# SCH_cool-title_2025-03-12.net
KiCad netlist of a schematic drawn in EasyEDA
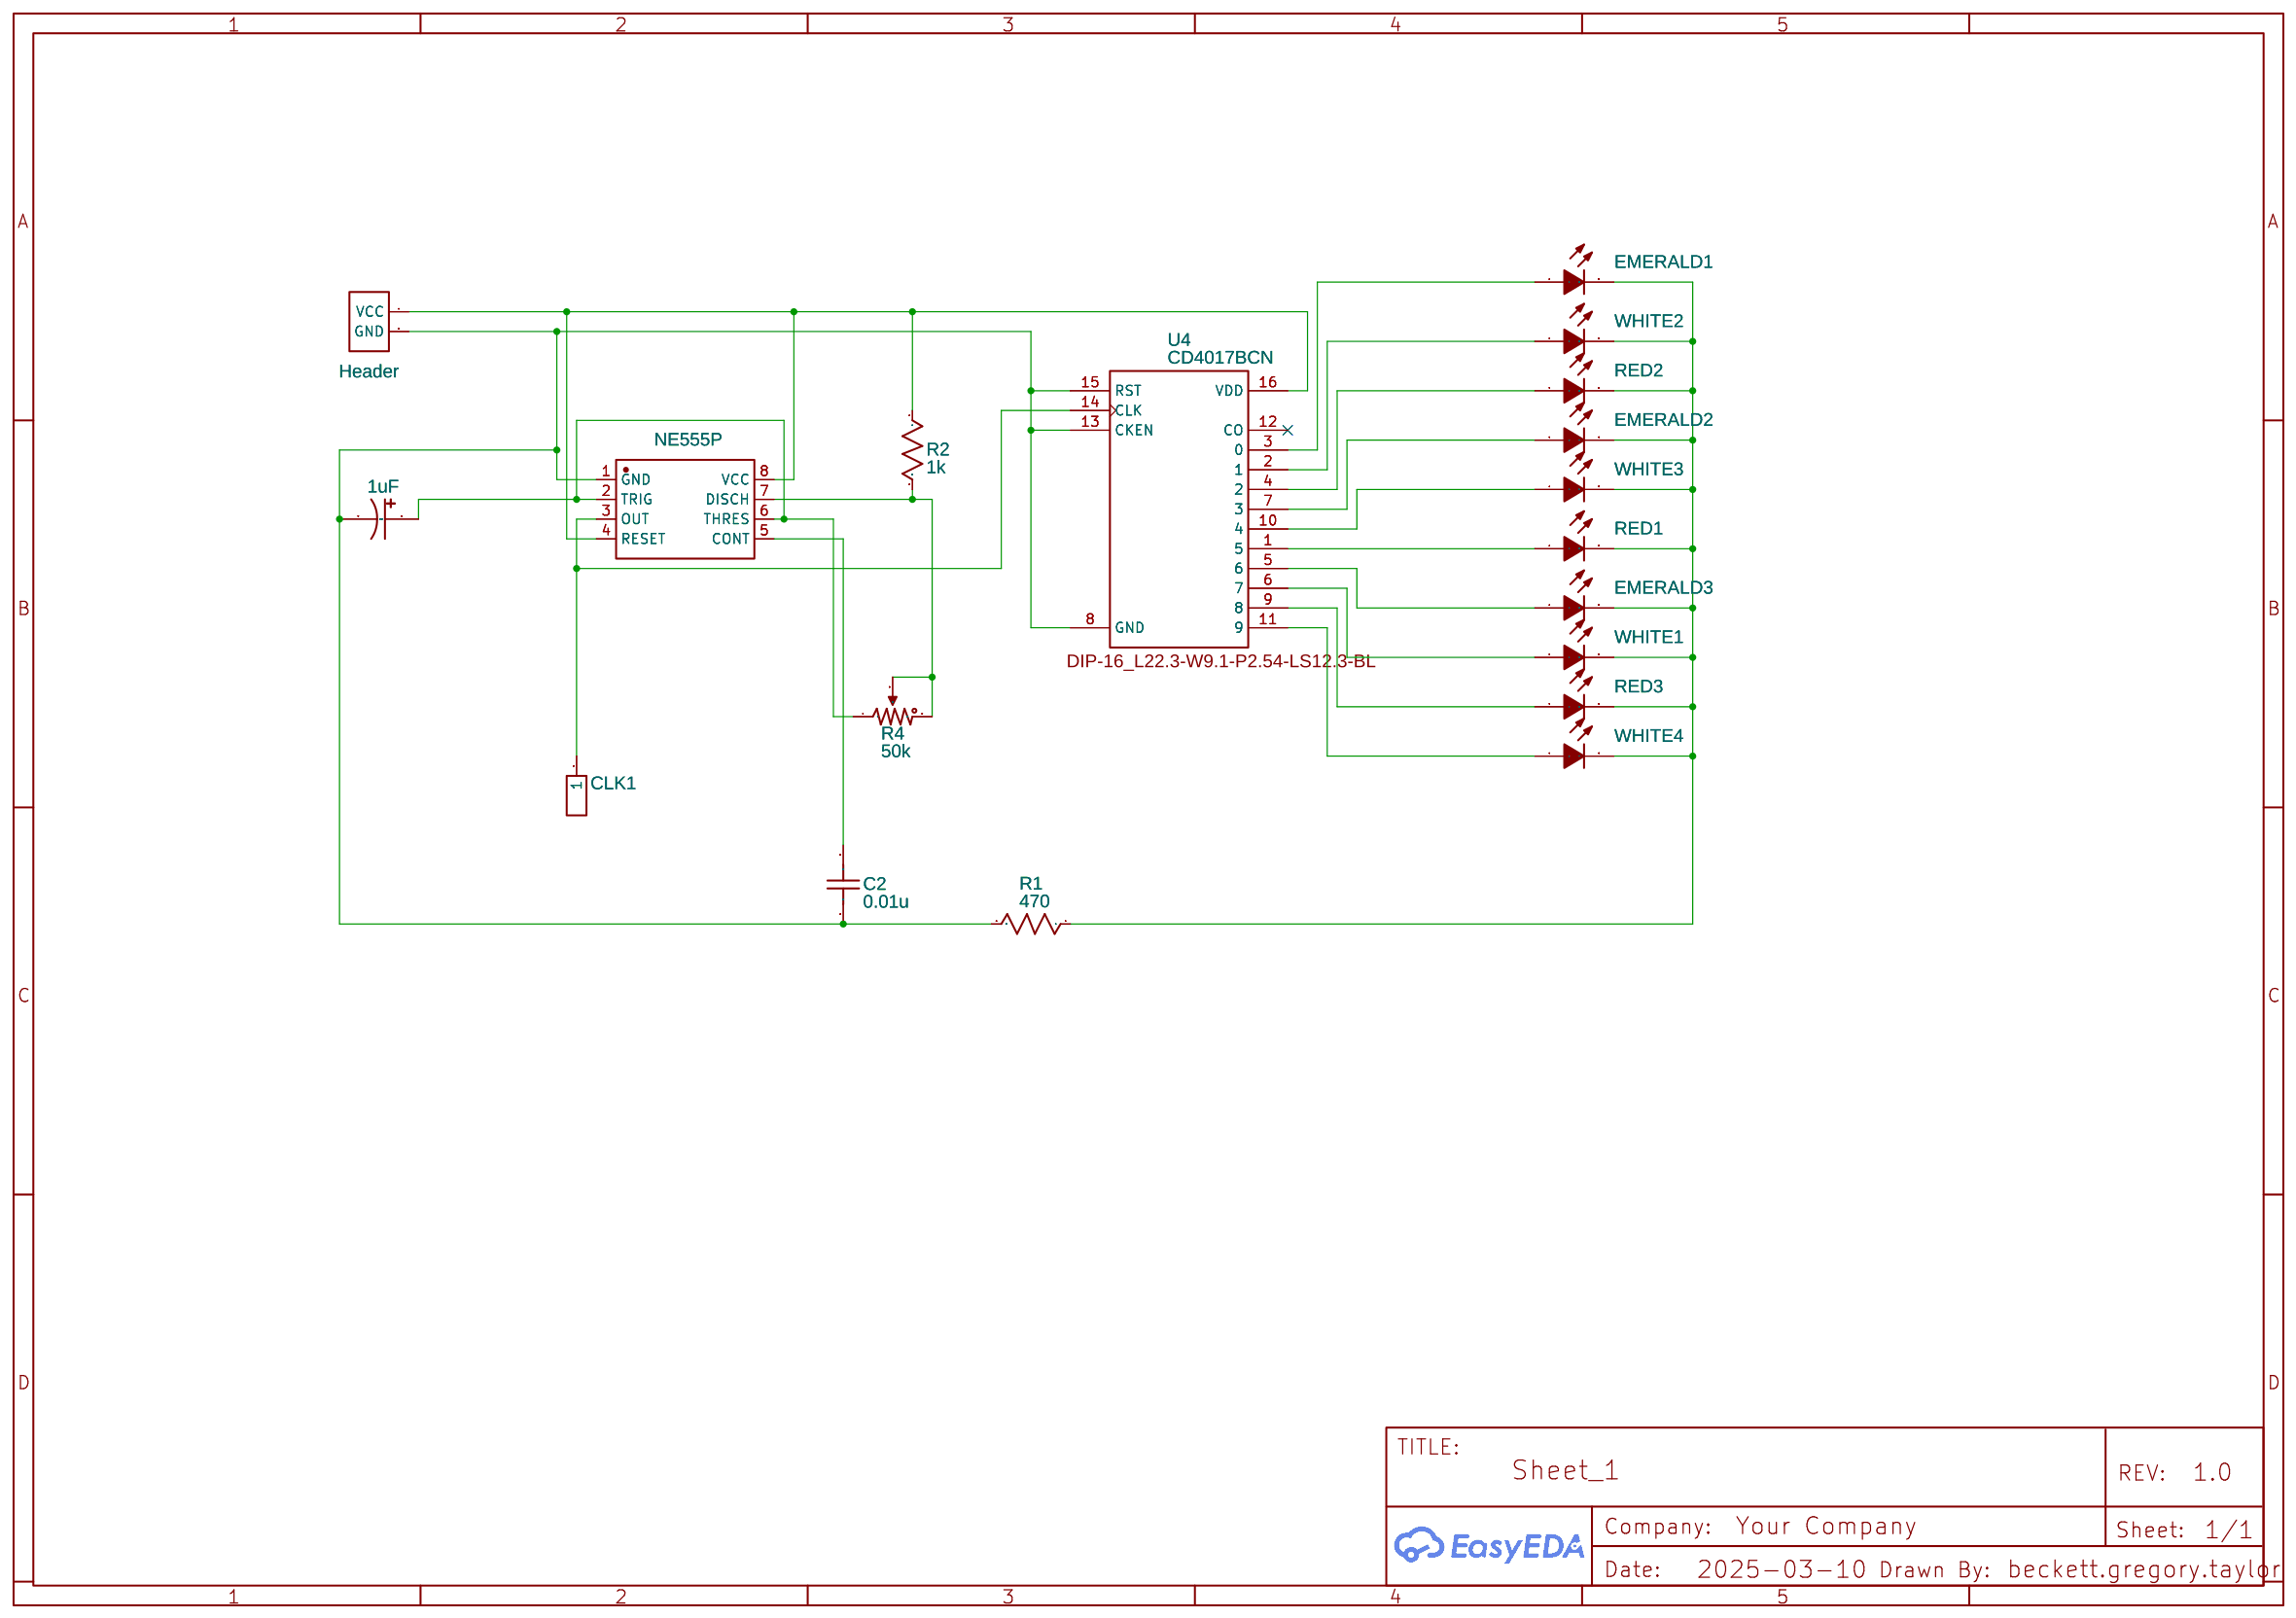
[diagram p0: schematic sheet]

(export (version "E")
  (design (tool "Eeschema 10.0.6"))
  (components
    (comp (ref "C1")
      (value "1uF")
      (fields (field (name "Manufacturer Part") "UVZ1H010MDD") (field (name "Manufacturer") "Nichicon(尼吉康)"))
      (libsource (lib "") (part "UVZ1H010MDD"))
    )
    (comp (ref "C2") (value "0.01u") (libsource (lib "") (part "C_0603_US")))
    (comp (ref "CLK1")
      (value "C81276")
      (fields
        (field (name "Manufacturer Part") "2.54-1*1P针")
        (field (name "Manufacturer") "BOOMELE(Boom Precision Elec)")
      )
      (libsource (lib "") (part "Header-Male-2.54_1x1"))
    )
    (comp (ref "EMERALD1") (value "LED_5MM") (libsource (lib "") (part "LED_5MM_2")))
    (comp (ref "EMERALD2") (value "LED_5MM") (libsource (lib "") (part "LED_5MM_2")))
    (comp (ref "EMERALD3") (value "LED_5MM") (libsource (lib "") (part "LED_5MM_2")))
    (comp (ref "H1") (value "Header") (libsource (lib "") (part "HEADER-FEMALE-2.54_1X2")))
    (comp (ref "R1")
      (value "470")
      (fields (field (name "Manufacturer Part") "?"))
      (libsource (lib "") (part "Resistor"))
    )
    (comp (ref "R2")
      (value "1k")
      (fields (field (name "Manufacturer Part") "?"))
      (libsource (lib "") (part "Resistor_1"))
    )
    (comp (ref "R4")
      (value "50k")
      (fields (field (name "Manufacturer Part") "?"))
      (libsource (lib "") (part "Potentiometer"))
    )
    (comp (ref "RED1") (value "LED_5MM") (libsource (lib "") (part "LED_5MM")))
    (comp (ref "RED2") (value "LED_5MM") (libsource (lib "") (part "LED_5MM")))
    (comp (ref "RED3") (value "LED_5MM") (libsource (lib "") (part "LED_5MM")))
    (comp (ref "U2")
      (value "NE555P")
      (fields (field (name "Manufacturer") "TI(德州仪器)"))
      (libsource (lib "") (part "NE555P"))
    )
    (comp (ref "U4") (value "CD4017BCN") (libsource (lib "") (part "CD4017BCN")))
    (comp (ref "WHITE1") (value "LED_5MM") (libsource (lib "") (part "LED_5MM_1")))
    (comp (ref "WHITE2") (value "LED_5MM") (libsource (lib "") (part "LED_5MM_1")))
    (comp (ref "WHITE3") (value "LED_5MM") (libsource (lib "") (part "LED_5MM_1")))
    (comp (ref "WHITE4") (value "LED_5MM") (libsource (lib "") (part "LED_5MM_1")))
  )
  (nets
    (net (code "1") (name "Net-(EMERALD1-A)") (class "Default")
      (node (ref "EMERALD1") (pin "1") (pinfunction "A_1") (pintype "input"))
      (node (ref "U4") (pin "3") (pinfunction "0_3") (pintype "output"))
    )
    (net (code "2") (name "Net-(EMERALD1-K)") (class "Default")
      (node (ref "EMERALD1") (pin "2") (pinfunction "K_2") (pintype "input"))
      (node (ref "EMERALD2") (pin "2") (pinfunction "K_2") (pintype "input"))
      (node (ref "EMERALD3") (pin "2") (pinfunction "K_2") (pintype "input"))
      (node (ref "R1") (pin "1") (pinfunction "1_1") (pintype "unspecified"))
      (node (ref "RED1") (pin "2") (pinfunction "K_2") (pintype "input"))
      (node (ref "RED2") (pin "2") (pinfunction "K_2") (pintype "input"))
      (node (ref "RED3") (pin "2") (pinfunction "K_2") (pintype "input"))
      (node (ref "WHITE1") (pin "2") (pinfunction "K_2") (pintype "input"))
      (node (ref "WHITE2") (pin "2") (pinfunction "K_2") (pintype "input"))
      (node (ref "WHITE3") (pin "2") (pinfunction "K_2") (pintype "input"))
      (node (ref "WHITE4") (pin "2") (pinfunction "K_2") (pintype "input"))
    )
    (net (code "3") (name "Net-(EMERALD2-A)") (class "Default")
      (node (ref "EMERALD2") (pin "1") (pinfunction "A_1") (pintype "input"))
      (node (ref "U4") (pin "7") (pinfunction "3_7") (pintype "output"))
    )
    (net (code "4") (name "Net-(EMERALD3-A)") (class "Default")
      (node (ref "EMERALD3") (pin "1") (pinfunction "A_1") (pintype "input"))
      (node (ref "U4") (pin "5") (pinfunction "6_5") (pintype "output"))
    )
    (net (code "5") (name "Net-(H1-GND)") (class "Default")
      (node (ref "C1") (pin "2") (pinfunction "2_2") (pintype "unspecified"))
      (node (ref "C2") (pin "1") (pinfunction "1_1") (pintype "unspecified"))
      (node (ref "H1") (pin "2") (pinfunction "GND_2") (pintype "unspecified"))
      (node (ref "R1") (pin "2") (pinfunction "2_2") (pintype "unspecified"))
      (node (ref "U2") (pin "1") (pinfunction "GND_1") (pintype "unspecified"))
      (node (ref "U4") (pin "13") (pinfunction "CKEN_13") (pintype "unspecified"))
      (node (ref "U4") (pin "15") (pinfunction "RST_15") (pintype "unspecified"))
      (node (ref "U4") (pin "8") (pinfunction "GND_8") (pintype "passive"))
    )
    (net (code "6") (name "Net-(H1-VCC)") (class "Default")
      (node (ref "H1") (pin "1") (pinfunction "VCC_1") (pintype "unspecified"))
      (node (ref "R2") (pin "1") (pinfunction "1_1") (pintype "unspecified"))
      (node (ref "U2") (pin "4") (pinfunction "RESET_4") (pintype "unspecified"))
      (node (ref "U2") (pin "8") (pinfunction "VCC_8") (pintype "unspecified"))
      (node (ref "U4") (pin "16") (pinfunction "VDD_16") (pintype "passive"))
    )
    (net (code "7") (name "Net-(R4-2)") (class "Default")
      (node (ref "R2") (pin "2") (pinfunction "2_2") (pintype "unspecified"))
      (node (ref "R4") (pin "2") (pinfunction "3_2") (pintype "unspecified"))
      (node (ref "R4") (pin "3") (pinfunction "2_3") (pintype "unspecified"))
      (node (ref "U2") (pin "7") (pinfunction "DISCH_7") (pintype "unspecified"))
    )
    (net (code "8") (name "Net-(RED1-A)") (class "Default")
      (node (ref "RED1") (pin "1") (pinfunction "A_1") (pintype "input"))
      (node (ref "U4") (pin "1") (pinfunction "5_1") (pintype "output"))
    )
    (net (code "9") (name "Net-(RED2-A)") (class "Default")
      (node (ref "RED2") (pin "1") (pinfunction "A_1") (pintype "input"))
      (node (ref "U4") (pin "4") (pinfunction "2_4") (pintype "output"))
    )
    (net (code "10") (name "Net-(RED3-A)") (class "Default")
      (node (ref "RED3") (pin "1") (pinfunction "A_1") (pintype "input"))
      (node (ref "U4") (pin "9") (pinfunction "8_9") (pintype "output"))
    )
    (net (code "11") (name "Net-(U2-CONT)") (class "Default")
      (node (ref "C2") (pin "2") (pinfunction "2_2") (pintype "unspecified"))
      (node (ref "U2") (pin "5") (pinfunction "CONT_5") (pintype "unspecified"))
    )
    (net (code "12") (name "Net-(U2-OUT)") (class "Default")
      (node (ref "CLK1") (pin "1") (pinfunction "1_1") (pintype "unspecified"))
      (node (ref "U2") (pin "3") (pinfunction "OUT_3") (pintype "unspecified"))
      (node (ref "U4") (pin "14") (pinfunction "CLK_14") (pintype "unspecified"))
    )
    (net (code "13") (name "Net-(U2-THRES)") (class "Default")
      (node (ref "C1") (pin "1") (pinfunction "1_1") (pintype "unspecified"))
      (node (ref "R4") (pin "1") (pinfunction "1_1") (pintype "unspecified"))
      (node (ref "U2") (pin "2") (pinfunction "TRIG_2") (pintype "unspecified"))
      (node (ref "U2") (pin "6") (pinfunction "THRES_6") (pintype "unspecified"))
    )
    (net (code "14") (name "Net-(U4-1)") (class "Default")
      (node (ref "U4") (pin "2") (pinfunction "1_2") (pintype "output"))
      (node (ref "WHITE2") (pin "1") (pinfunction "A_1") (pintype "input"))
    )
    (net (code "15") (name "Net-(U4-4)") (class "Default")
      (node (ref "U4") (pin "10") (pinfunction "4_10") (pintype "output"))
      (node (ref "WHITE3") (pin "1") (pinfunction "A_1") (pintype "input"))
    )
    (net (code "16") (name "Net-(U4-7)") (class "Default")
      (node (ref "U4") (pin "6") (pinfunction "7_6") (pintype "output"))
      (node (ref "WHITE1") (pin "1") (pinfunction "A_1") (pintype "input"))
    )
    (net (code "17") (name "Net-(U4-9)") (class "Default")
      (node (ref "U4") (pin "11") (pinfunction "9_11") (pintype "output"))
      (node (ref "WHITE4") (pin "1") (pinfunction "A_1") (pintype "input"))
    )
    (net (code "18") (name "unconnected-(U4-CO-Pad12)") (class "Default")
      (node (ref "U4") (pin "12") (pinfunction "CO_12") (pintype "output+no_connect"))
    )
  )
)
